# obc-v2_USB-HUB.net
KiCad netlist of a schematic drawn in Altium Designer
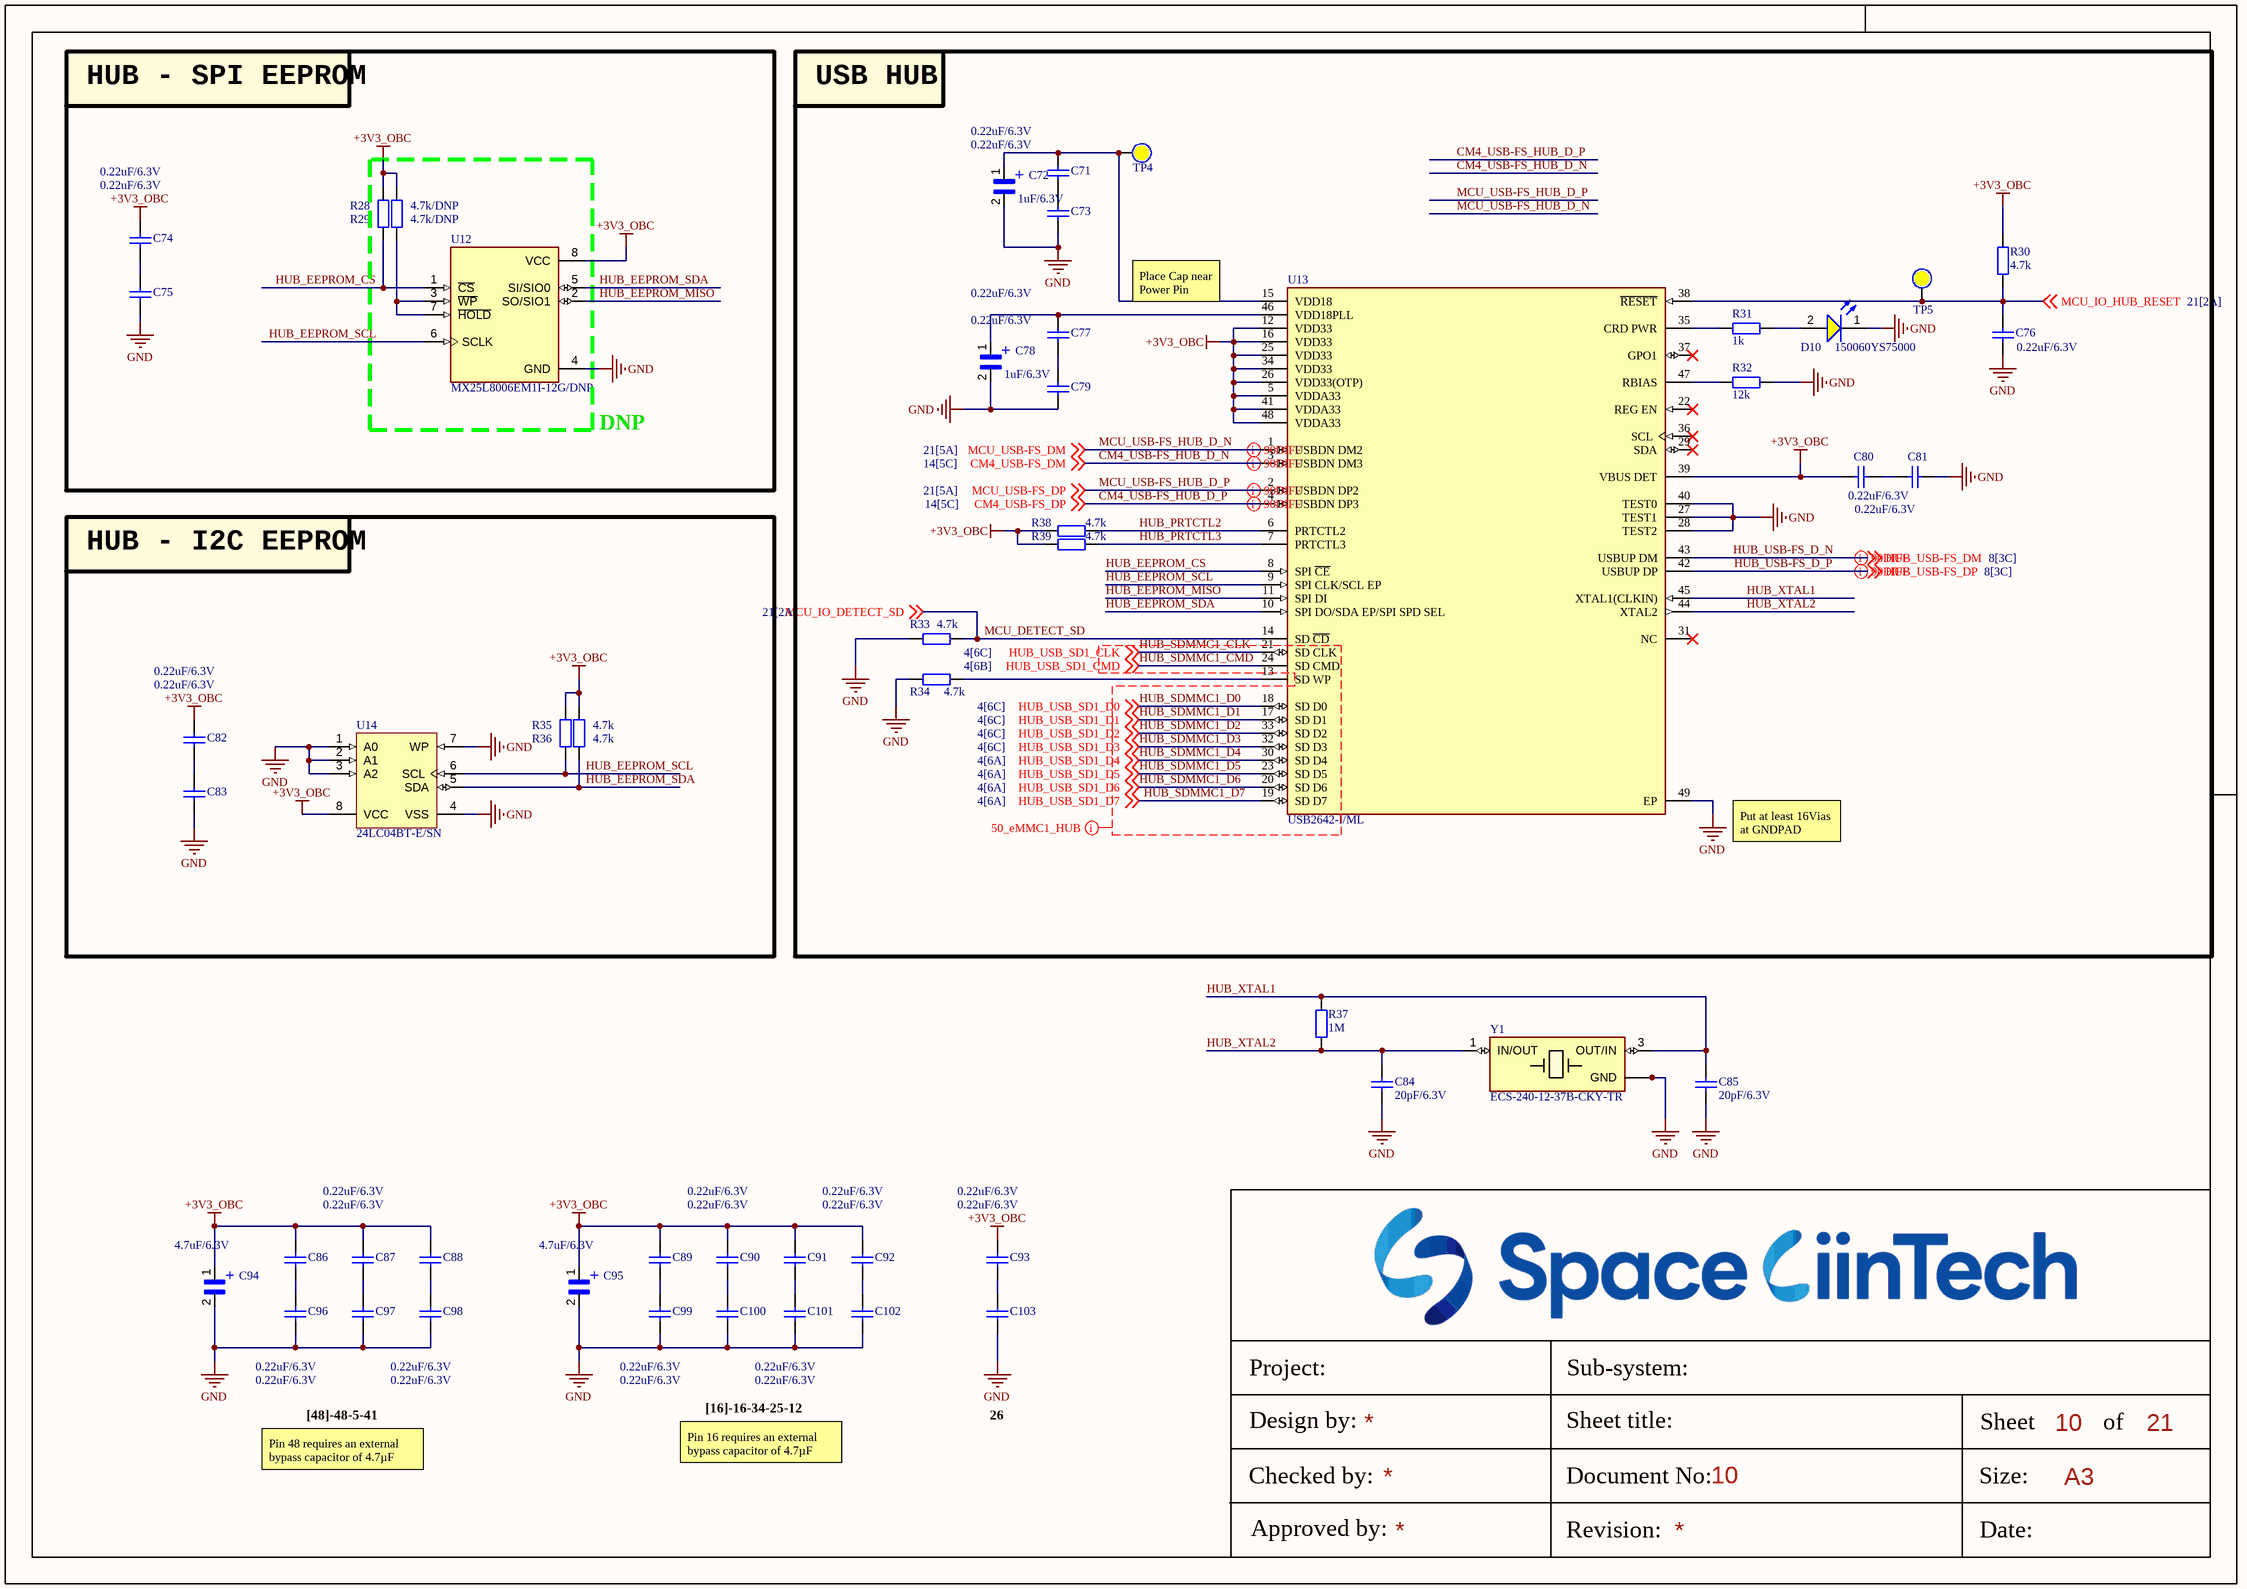
[diagram p0: obc-v2_USB-HUB.SchDoc]

(export (version "E")
  (design (tool "Eeschema 10.0.6"))
  (components
    (comp (ref "C71")
      (value "0.22uF/6.3V")
      (footprint "CAP_C_1005X60")
      (description "CAPC")
      (libsource (lib "Altium_Lib_by_KhueNguyenCreator") (part "Tu 0402 33nF 10V"))
    )
    (comp (ref "C72")
      (value "1uF/6.3V")
      (footprint "CAP_MP_1608X90")
      (description "CAPP")
      (fields (field (name "MP") "TACL335M003RTA"))
      (libsource (lib "TACL335M003RTA") (part "TACL335M003RTA"))
    )
    (comp (ref "C73")
      (value "0.22uF/6.3V")
      (footprint "CAP_C_1005X60")
      (description "CAPC")
      (libsource (lib "Altium_Lib_by_KhueNguyenCreator") (part "Tu 0402 33nF 10V"))
    )
    (comp (ref "C74")
      (value "0.22uF/6.3V")
      (footprint "CAP_C_1005X60")
      (description "CAPC")
      (libsource (lib "Altium_Lib_by_KhueNguyenCreator") (part "Tu 0402 33nF 10V"))
    )
    (comp (ref "C75")
      (value "0.22uF/6.3V")
      (footprint "CAP_C_1005X60")
      (description "CAPC")
      (libsource (lib "Altium_Lib_by_KhueNguyenCreator") (part "Tu 0402 33nF 10V"))
    )
    (comp (ref "C76")
      (value "0.22uF/6.3V")
      (footprint "CAP_C_1005X60")
      (description "CAPC")
      (libsource (lib "Altium_Lib_by_KhueNguyenCreator") (part "Tu 0402 33nF 10V"))
    )
    (comp (ref "C77")
      (value "0.22uF/6.3V")
      (footprint "CAP_C_1005X60")
      (description "CAPC")
      (libsource (lib "Altium_Lib_by_KhueNguyenCreator") (part "Tu 0402 33nF 10V"))
    )
    (comp (ref "C78")
      (value "1uF/6.3V")
      (footprint "CAP_MP_1608X90")
      (description "CAPP")
      (fields (field (name "MP") "TACL335M003RTA"))
      (libsource (lib "TACL335M003RTA") (part "TACL335M003RTA"))
    )
    (comp (ref "C79")
      (value "0.22uF/6.3V")
      (footprint "CAP_C_1005X60")
      (description "CAPC")
      (libsource (lib "Altium_Lib_by_KhueNguyenCreator") (part "Tu 0402 33nF 10V"))
    )
    (comp (ref "C80")
      (value "0.22uF/6.3V")
      (footprint "CAP_C_1005X60")
      (description "CAPC")
      (libsource (lib "Altium_Lib_by_KhueNguyenCreator") (part "Tu 0402 33nF 10V"))
    )
    (comp (ref "C81")
      (value "0.22uF/6.3V")
      (footprint "CAP_C_1005X60")
      (description "CAPC")
      (libsource (lib "Altium_Lib_by_KhueNguyenCreator") (part "Tu 0402 33nF 10V"))
    )
    (comp (ref "C82")
      (value "0.22uF/6.3V")
      (footprint "CAP_C_1005X60")
      (description "CAPC")
      (libsource (lib "Altium_Lib_by_KhueNguyenCreator") (part "Tu 0402 33nF 10V"))
    )
    (comp (ref "C83")
      (value "0.22uF/6.3V")
      (footprint "CAP_C_1005X60")
      (description "CAPC")
      (libsource (lib "Altium_Lib_by_KhueNguyenCreator") (part "Tu 0402 33nF 10V"))
    )
    (comp (ref "C84")
      (value "20pF/6.3V")
      (footprint "CAP_C_1005X60")
      (description "CAPC")
      (libsource (lib "Altium_Lib_by_KhueNguyenCreator") (part "Tu 0402 33nF 10V"))
    )
    (comp (ref "C85")
      (value "20pF/6.3V")
      (footprint "CAP_C_1005X60")
      (description "CAPC")
      (libsource (lib "Altium_Lib_by_KhueNguyenCreator") (part "Tu 0402 33nF 10V"))
    )
    (comp (ref "C86")
      (value "0.22uF/6.3V")
      (footprint "CAP_C_1005X60")
      (description "CAPC")
      (libsource (lib "Altium_Lib_by_KhueNguyenCreator") (part "Tu 0402 33nF 10V"))
    )
    (comp (ref "C87")
      (value "0.22uF/6.3V")
      (footprint "CAP_C_1005X60")
      (description "CAPC")
      (libsource (lib "Altium_Lib_by_KhueNguyenCreator") (part "Tu 0402 33nF 10V"))
    )
    (comp (ref "C88")
      (value "0.22uF/6.3V")
      (footprint "CAP_C_1005X60")
      (description "CAPC")
      (libsource (lib "Altium_Lib_by_KhueNguyenCreator") (part "Tu 0402 33nF 10V"))
    )
    (comp (ref "C89")
      (value "0.22uF/6.3V")
      (footprint "CAP_C_1005X60")
      (description "CAPC")
      (libsource (lib "Altium_Lib_by_KhueNguyenCreator") (part "Tu 0402 33nF 10V"))
    )
    (comp (ref "C90")
      (value "0.22uF/6.3V")
      (footprint "CAP_C_1005X60")
      (description "CAPC")
      (libsource (lib "Altium_Lib_by_KhueNguyenCreator") (part "Tu 0402 33nF 10V"))
    )
    (comp (ref "C91")
      (value "0.22uF/6.3V")
      (footprint "CAP_C_1005X60")
      (description "CAPC")
      (libsource (lib "Altium_Lib_by_KhueNguyenCreator") (part "Tu 0402 33nF 10V"))
    )
    (comp (ref "C92")
      (value "0.22uF/6.3V")
      (footprint "CAP_C_1005X60")
      (description "CAPC")
      (libsource (lib "Altium_Lib_by_KhueNguyenCreator") (part "Tu 0402 33nF 10V"))
    )
    (comp (ref "C93")
      (value "0.22uF/6.3V")
      (footprint "CAP_C_1005X60")
      (description "CAPC")
      (libsource (lib "Altium_Lib_by_KhueNguyenCreator") (part "Tu 0402 33nF 10V"))
    )
    (comp (ref "C94")
      (value "4.7uF/6.3V")
      (footprint "CAP_MP_1608X90")
      (description "CAPP")
      (fields (field (name "MP") "TACL335M003RTA"))
      (libsource (lib "TACL335M003RTA") (part "TACL335M003RTA"))
    )
    (comp (ref "C95")
      (value "4.7uF/6.3V")
      (footprint "CAP_MP_1608X90")
      (description "CAPP")
      (fields (field (name "MP") "TACL335M003RTA"))
      (libsource (lib "TACL335M003RTA") (part "TACL335M003RTA"))
    )
    (comp (ref "C96")
      (value "0.22uF/6.3V")
      (footprint "CAP_C_1005X60")
      (description "CAPC")
      (libsource (lib "Altium_Lib_by_KhueNguyenCreator") (part "Tu 0402 33nF 10V"))
    )
    (comp (ref "C97")
      (value "0.22uF/6.3V")
      (footprint "CAP_C_1005X60")
      (description "CAPC")
      (libsource (lib "Altium_Lib_by_KhueNguyenCreator") (part "Tu 0402 33nF 10V"))
    )
    (comp (ref "C98")
      (value "0.22uF/6.3V")
      (footprint "CAP_C_1005X60")
      (description "CAPC")
      (libsource (lib "Altium_Lib_by_KhueNguyenCreator") (part "Tu 0402 33nF 10V"))
    )
    (comp (ref "C99")
      (value "0.22uF/6.3V")
      (footprint "CAP_C_1005X60")
      (description "CAPC")
      (libsource (lib "Altium_Lib_by_KhueNguyenCreator") (part "Tu 0402 33nF 10V"))
    )
    (comp (ref "C100")
      (value "0.22uF/6.3V")
      (footprint "CAP_C_1005X60")
      (description "CAPC")
      (libsource (lib "Altium_Lib_by_KhueNguyenCreator") (part "Tu 0402 33nF 10V"))
    )
    (comp (ref "C101")
      (value "0.22uF/6.3V")
      (footprint "CAP_C_1005X60")
      (description "CAPC")
      (libsource (lib "Altium_Lib_by_KhueNguyenCreator") (part "Tu 0402 33nF 10V"))
    )
    (comp (ref "C102")
      (value "0.22uF/6.3V")
      (footprint "CAP_C_1005X60")
      (description "CAPC")
      (libsource (lib "Altium_Lib_by_KhueNguyenCreator") (part "Tu 0402 33nF 10V"))
    )
    (comp (ref "C103")
      (value "0.22uF/6.3V")
      (footprint "CAP_C_1005X60")
      (description "CAPC")
      (libsource (lib "Altium_Lib_by_KhueNguyenCreator") (part "Tu 0402 33nF 10V"))
    )
    (comp (ref "D10")
      (value "150060YS75000")
      (footprint "WL-SMCW_0603_150060xx75000")
      (description "LED YELLOW CLEAR 0603 SMD")
      (libsource (lib "Altium Content Vault") (part "LED_Yellow_2A-1K"))
    )
    (comp (ref "R28")
      (value "4.7k/DNP")
      (footprint "RES_C_1608X60")
      (description "RES")
      (libsource (lib "Altium_Lib_by_KhueNguyenCreator") (part "Tro 0603 1% 10k"))
    )
    (comp (ref "R29")
      (value "4.7k/DNP")
      (footprint "RES_C_1608X60")
      (description "RES")
      (libsource (lib "Altium_Lib_by_KhueNguyenCreator") (part "Tro 0603 1% 10k"))
    )
    (comp (ref "R30")
      (value "4.7k")
      (footprint "RES_C_1608X60")
      (description "RES")
      (libsource (lib "Altium_Lib_by_KhueNguyenCreator") (part "Tro 0603 1% 10k"))
    )
    (comp (ref "R31")
      (value "1k")
      (footprint "RES_C_1608X60")
      (description "RES")
      (libsource (lib "Altium_Lib_by_KhueNguyenCreator") (part "Tro 0603 1% 10k"))
    )
    (comp (ref "R32")
      (value "12k")
      (footprint "RES_C_1608X60")
      (description "RES SMD 12K OHM 1% 1/10W 0603, P/N: ERJ-3EKF1202V")
      (libsource (lib "Altium_Lib_by_KhueNguyenCreator") (part "Tro 0603 1% 1k"))
    )
    (comp (ref "R33")
      (value "4.7k")
      (footprint "RES_C_1608X60")
      (description "RES")
      (libsource (lib "Altium_Lib_by_KhueNguyenCreator") (part "Tro 0603 1% 10k"))
    )
    (comp (ref "R34")
      (value "4.7k")
      (footprint "RES_C_1608X60")
      (description "RES")
      (libsource (lib "Altium_Lib_by_KhueNguyenCreator") (part "Tro 0603 1% 10k"))
    )
    (comp (ref "R35")
      (value "4.7k")
      (footprint "RES_C_1608X60")
      (description "RES")
      (libsource (lib "Altium_Lib_by_KhueNguyenCreator") (part "Tro 0603 1% 10k"))
    )
    (comp (ref "R36")
      (value "4.7k")
      (footprint "RES_C_1608X60")
      (description "RES")
      (libsource (lib "Altium_Lib_by_KhueNguyenCreator") (part "Tro 0603 1% 10k"))
    )
    (comp (ref "R37")
      (value "1M")
      (footprint "RES_C_1608X60")
      (description "RES SMD 12K OHM 1% 1/10W 0603, P/N: ERJ-3EKF1202V")
      (libsource (lib "Altium_Lib_by_KhueNguyenCreator") (part "Tro 0603 1% 1k"))
    )
    (comp (ref "R38")
      (value "4.7k")
      (footprint "RES_C_1608X60")
      (description "RES")
      (libsource (lib "Altium_Lib_by_KhueNguyenCreator") (part "Tro 0603 1% 10k"))
    )
    (comp (ref "R39")
      (value "4.7k")
      (footprint "RES_C_1608X60")
      (description "RES")
      (libsource (lib "Altium_Lib_by_KhueNguyenCreator") (part "Tro 0603 1% 10k"))
    )
    (comp (ref "TP4")
      (value "~")
      (footprint "Test Point 1 Side")
      (description "Test Point")
      (libsource (lib "BYTECH_HW_LIB_2019 (1)") (part "Test Point"))
    )
    (comp (ref "TP5")
      (value "~")
      (footprint "Test Point 1 Side")
      (description "Test Point")
      (libsource (lib "") (part "Test Point_1"))
    )
    (comp (ref "U12")
      (value "MX25L8006EM1I-12G/DNP")
      (footprint "SOIC127P602X173-8N")
      (description "FLASH - NOR Memory IC 8Mb (1M x 8) SPI 86 MHz 8-SOP")
      (fields (field (name "MF") "Macronix") (field (name "MP") "MX25L8006EM1I-12G"))
      (libsource (lib "MX25L8006EM1I-12G") (part "MX25L8006EM1I-12G"))
    )
    (comp (ref "U13")
      (value "USB2642-I/ML")
      (footprint "FP-48QFN-5304-7x7B-IPC_A")
      (description "IC INTERFACE SPECIALIZED 48QFN")
      (libsource (lib "Altium Content Vault") (part "374cda126ac25a5c5b8599f60553335"))
    )
    (comp (ref "U14")
      (value "24LC04BT-E/SN")
      (footprint "SOIC-SN8_L")
      (description "4Kbit, 400kHz, 2.5V, I2C Serial EEPROM, 8-Pin SOIC 150mil, Extended Temperature, Tape and Reel")
      (libsource (lib "Altium Content Vault") (part "MEM-SEEPROM-34AA02-IL8"))
    )
    (comp (ref "Y1")
      (value "ECS-240-12-37B-CKY-TR")
      (footprint "XTAL_ECS-240-12-37B-CKY-TR")
      (libsource (lib "ECS-240-12-37B-CKY-TR") (part "ECS-240-12-37B-CKY-TR"))
    )
  )
  (nets
    (net (code "1") (name "+3V3_OBC") (class "Default")
      (node (ref "C74") (pin "1") (pinfunction "1_1") (pintype "passive"))
      (node (ref "C80") (pin "1") (pinfunction "1_1") (pintype "passive"))
      (node (ref "C82") (pin "1") (pinfunction "1_1") (pintype "passive"))
      (node (ref "C86") (pin "1") (pinfunction "1_1") (pintype "passive"))
      (node (ref "C87") (pin "1") (pinfunction "1_1") (pintype "passive"))
      (node (ref "C88") (pin "1") (pinfunction "1_1") (pintype "passive"))
      (node (ref "C89") (pin "1") (pinfunction "1_1") (pintype "passive"))
      (node (ref "C90") (pin "1") (pinfunction "1_1") (pintype "passive"))
      (node (ref "C91") (pin "1") (pinfunction "1_1") (pintype "passive"))
      (node (ref "C92") (pin "1") (pinfunction "1_1") (pintype "passive"))
      (node (ref "C93") (pin "1") (pinfunction "1_1") (pintype "passive"))
      (node (ref "C94") (pin "1") (pinfunction "1_1") (pintype "passive"))
      (node (ref "C95") (pin "1") (pinfunction "1_1") (pintype "passive"))
      (node (ref "R28") (pin "2") (pinfunction "2_2") (pintype "passive"))
      (node (ref "R29") (pin "2") (pinfunction "2_2") (pintype "passive"))
      (node (ref "R30") (pin "1") (pinfunction "1_1") (pintype "passive"))
      (node (ref "R35") (pin "2") (pinfunction "2_2") (pintype "passive"))
      (node (ref "R36") (pin "2") (pinfunction "2_2") (pintype "passive"))
      (node (ref "R38") (pin "1") (pinfunction "1_1") (pintype "passive"))
      (node (ref "R39") (pin "1") (pinfunction "1_1") (pintype "passive"))
      (node (ref "U12") (pin "8") (pinfunction "VCC_8") (pintype "power_in"))
      (node (ref "U13") (pin "12") (pinfunction "VDD33_12") (pintype "power_in"))
      (node (ref "U13") (pin "16") (pinfunction "VDD33_16") (pintype "power_in"))
      (node (ref "U13") (pin "25") (pinfunction "VDD33_25") (pintype "power_in"))
      (node (ref "U13") (pin "26") (pinfunction "VDD33(OTP)_26") (pintype "power_in"))
      (node (ref "U13") (pin "34") (pinfunction "VDD33_34") (pintype "power_in"))
      (node (ref "U13") (pin "39") (pinfunction "VBUS_DET_39") (pintype "power_in"))
      (node (ref "U13") (pin "41") (pinfunction "VDDA33_41") (pintype "power_in"))
      (node (ref "U13") (pin "48") (pinfunction "VDDA33_48") (pintype "power_in"))
      (node (ref "U13") (pin "5") (pinfunction "VDDA33_5") (pintype "power_in"))
      (node (ref "U14") (pin "8") (pinfunction "VCC_8") (pintype "power_in"))
    )
    (net (code "2") (name "/HUB_EEPROM_CS") (class "Default")
      (node (ref "R29") (pin "1") (pinfunction "1_1") (pintype "passive"))
      (node (ref "U12") (pin "1") (pinfunction "~{CS}_1") (pintype "input"))
      (node (ref "U13") (pin "8") (pinfunction "SPI_~{CE}_8") (pintype "input"))
    )
    (net (code "3") (name "/HUB_EEPROM_MISO") (class "Default")
      (node (ref "U12") (pin "2") (pinfunction "SO/SIO1_2") (pintype "bidirectional"))
      (node (ref "U13") (pin "11") (pinfunction "SPI_DI_11") (pintype "input"))
    )
    (net (code "4") (name "/HUB_EEPROM_SCL") (class "Default")
      (node (ref "R36") (pin "1") (pinfunction "1_1") (pintype "passive"))
      (node (ref "U12") (pin "6") (pinfunction "SCLK_6") (pintype "input"))
      (node (ref "U13") (pin "9") (pinfunction "SPI_CLK/SCL_EP_9") (pintype "input"))
      (node (ref "U14") (pin "6") (pinfunction "SCL_6") (pintype "input"))
    )
    (net (code "5") (name "/HUB_EEPROM_SDA") (class "Default")
      (node (ref "R35") (pin "1") (pinfunction "1_1") (pintype "passive"))
      (node (ref "U12") (pin "5") (pinfunction "SI/SIO0_5") (pintype "bidirectional"))
      (node (ref "U13") (pin "10") (pinfunction "SPI_DO/SDA_EP/SPI_SPD_SEL_10") (pintype "input"))
      (node (ref "U14") (pin "5") (pinfunction "SDA_5") (pintype "bidirectional"))
    )
    (net (code "6") (name "/HUB_PRTCTL2") (class "Default")
      (node (ref "R38") (pin "2") (pinfunction "2_2") (pintype "passive"))
      (node (ref "U13") (pin "6") (pinfunction "PRTCTL2_6") (pintype "passive"))
    )
    (net (code "7") (name "/HUB_PRTCTL3") (class "Default")
      (node (ref "R39") (pin "2") (pinfunction "2_2") (pintype "passive"))
      (node (ref "U13") (pin "7") (pinfunction "PRTCTL3_7") (pintype "passive"))
    )
    (net (code "8") (name "/HUB_XTAL1") (class "Default")
      (node (ref "C85") (pin "2") (pinfunction "2_2") (pintype "passive"))
      (node (ref "R37") (pin "2") (pinfunction "2_2") (pintype "passive"))
      (node (ref "U13") (pin "45") (pinfunction "XTAL1(CLKIN)_45") (pintype "input"))
      (node (ref "Y1") (pin "3") (pinfunction "OUT/IN_3") (pintype "bidirectional"))
    )
    (net (code "9") (name "/HUB_XTAL2") (class "Default")
      (node (ref "C84") (pin "2") (pinfunction "2_2") (pintype "passive"))
      (node (ref "R37") (pin "1") (pinfunction "1_1") (pintype "passive"))
      (node (ref "U13") (pin "44") (pinfunction "XTAL2_44") (pintype "output"))
      (node (ref "Y1") (pin "1") (pinfunction "IN/OUT_1") (pintype "bidirectional"))
    )
    (net (code "10") (name "CM4_USB-FS_DM") (class "Default")
      (node (ref "U13") (pin "3") (pinfunction "USBDN_DM3_3") (pintype "bidirectional"))
    )
    (net (code "11") (name "CM4_USB-FS_DP") (class "Default")
      (node (ref "U13") (pin "4") (pinfunction "USBDN_DP3_4") (pintype "bidirectional"))
    )
    (net (code "12") (name "GND") (class "Default")
      (node (ref "C100") (pin "2") (pinfunction "2_2") (pintype "passive"))
      (node (ref "C101") (pin "2") (pinfunction "2_2") (pintype "passive"))
      (node (ref "C102") (pin "2") (pinfunction "2_2") (pintype "passive"))
      (node (ref "C103") (pin "2") (pinfunction "2_2") (pintype "passive"))
      (node (ref "C72") (pin "2") (pinfunction "2_2") (pintype "passive"))
      (node (ref "C73") (pin "1") (pinfunction "1_1") (pintype "passive"))
      (node (ref "C75") (pin "2") (pinfunction "2_2") (pintype "passive"))
      (node (ref "C76") (pin "2") (pinfunction "2_2") (pintype "passive"))
      (node (ref "C78") (pin "2") (pinfunction "2_2") (pintype "passive"))
      (node (ref "C79") (pin "1") (pinfunction "1_1") (pintype "passive"))
      (node (ref "C81") (pin "2") (pinfunction "2_2") (pintype "passive"))
      (node (ref "C83") (pin "2") (pinfunction "2_2") (pintype "passive"))
      (node (ref "C84") (pin "1") (pinfunction "1_1") (pintype "passive"))
      (node (ref "C85") (pin "1") (pinfunction "1_1") (pintype "passive"))
      (node (ref "C94") (pin "2") (pinfunction "2_2") (pintype "passive"))
      (node (ref "C95") (pin "2") (pinfunction "2_2") (pintype "passive"))
      (node (ref "C96") (pin "2") (pinfunction "2_2") (pintype "passive"))
      (node (ref "C97") (pin "2") (pinfunction "2_2") (pintype "passive"))
      (node (ref "C98") (pin "2") (pinfunction "2_2") (pintype "passive"))
      (node (ref "C99") (pin "2") (pinfunction "2_2") (pintype "passive"))
      (node (ref "D10") (pin "1") (pinfunction "K_1") (pintype "passive"))
      (node (ref "R32") (pin "2") (pinfunction "2_2") (pintype "passive"))
      (node (ref "R33") (pin "1") (pinfunction "1_1") (pintype "passive"))
      (node (ref "R34") (pin "1") (pinfunction "1_1") (pintype "passive"))
      (node (ref "U12") (pin "4") (pinfunction "GND_4") (pintype "power_in"))
      (node (ref "U13") (pin "27") (pinfunction "TEST1_27") (pintype "passive"))
      (node (ref "U13") (pin "28") (pinfunction "TEST2_28") (pintype "passive"))
      (node (ref "U13") (pin "40") (pinfunction "TEST0_40") (pintype "passive"))
      (node (ref "U13") (pin "49") (pinfunction "EP_49") (pintype "power_in"))
      (node (ref "U14") (pin "1") (pinfunction "A0_1") (pintype "input"))
      (node (ref "U14") (pin "2") (pinfunction "A1_2") (pintype "input"))
      (node (ref "U14") (pin "3") (pinfunction "A2_3") (pintype "input"))
      (node (ref "U14") (pin "4") (pinfunction "VSS_4") (pintype "power_in"))
      (node (ref "U14") (pin "7") (pinfunction "WP_7") (pintype "input"))
      (node (ref "Y1") (pin "2") (pinfunction "GND_2") (pintype "power_in"))
      (node (ref "Y1") (pin "4") (pinfunction "GND_4") (pintype "power_in"))
    )
    (net (code "13") (name "HUB_USB-FS_DM") (class "Default")
      (node (ref "U13") (pin "43") (pinfunction "USBUP_DM_43") (pintype "passive"))
    )
    (net (code "14") (name "HUB_USB-FS_DP") (class "Default")
      (node (ref "U13") (pin "42") (pinfunction "USBUP_DP_42") (pintype "passive"))
    )
    (net (code "15") (name "HUB_USB_SD1_CLK") (class "Default")
      (node (ref "U13") (pin "21") (pinfunction "SD_CLK_21") (pintype "bidirectional"))
    )
    (net (code "16") (name "HUB_USB_SD1_CMD") (class "Default")
      (node (ref "U13") (pin "24") (pinfunction "SD_CMD_24") (pintype "passive"))
    )
    (net (code "17") (name "HUB_USB_SD1_D0") (class "Default")
      (node (ref "U13") (pin "18") (pinfunction "SD_D0_18") (pintype "bidirectional"))
    )
    (net (code "18") (name "HUB_USB_SD1_D1") (class "Default")
      (node (ref "U13") (pin "17") (pinfunction "SD_D1_17") (pintype "bidirectional"))
    )
    (net (code "19") (name "HUB_USB_SD1_D2") (class "Default")
      (node (ref "U13") (pin "33") (pinfunction "SD_D2_33") (pintype "bidirectional"))
    )
    (net (code "20") (name "HUB_USB_SD1_D3") (class "Default")
      (node (ref "U13") (pin "32") (pinfunction "SD_D3_32") (pintype "bidirectional"))
    )
    (net (code "21") (name "HUB_USB_SD1_D4") (class "Default")
      (node (ref "U13") (pin "30") (pinfunction "SD_D4_30") (pintype "bidirectional"))
    )
    (net (code "22") (name "HUB_USB_SD1_D5") (class "Default")
      (node (ref "U13") (pin "23") (pinfunction "SD_D5_23") (pintype "bidirectional"))
    )
    (net (code "23") (name "HUB_USB_SD1_D6") (class "Default")
      (node (ref "U13") (pin "20") (pinfunction "SD_D6_20") (pintype "bidirectional"))
    )
    (net (code "24") (name "HUB_USB_SD1_D7") (class "Default")
      (node (ref "U13") (pin "19") (pinfunction "SD_D7_19") (pintype "bidirectional"))
    )
    (net (code "25") (name "MCU_IO_DETECT_SD") (class "Default")
      (node (ref "R33") (pin "2") (pinfunction "2_2") (pintype "passive"))
      (node (ref "U13") (pin "14") (pinfunction "SD_~{CD}_14") (pintype "passive"))
    )
    (net (code "26") (name "MCU_IO_HUB_RESET") (class "Default")
      (node (ref "C76") (pin "1") (pinfunction "1_1") (pintype "passive"))
      (node (ref "R30") (pin "2") (pinfunction "2_2") (pintype "passive"))
      (node (ref "TP5") (pin "0") (pinfunction "0_0") (pintype "passive"))
      (node (ref "U13") (pin "38") (pinfunction "~{RESET}_38") (pintype "input"))
    )
    (net (code "27") (name "MCU_USB-FS_DM") (class "Default")
      (node (ref "U13") (pin "1") (pinfunction "USBDN_DM2_1") (pintype "bidirectional"))
    )
    (net (code "28") (name "MCU_USB-FS_DP") (class "Default")
      (node (ref "U13") (pin "2") (pinfunction "USBDN_DP2_2") (pintype "bidirectional"))
    )
    (net (code "29") (name "Net-(C71-Pad1)") (class "Default")
      (node (ref "C71") (pin "1") (pinfunction "1_1") (pintype "passive"))
      (node (ref "C73") (pin "2") (pinfunction "2_2") (pintype "passive"))
    )
    (net (code "30") (name "Net-(C74-Pad2)") (class "Default")
      (node (ref "C74") (pin "2") (pinfunction "2_2") (pintype "passive"))
      (node (ref "C75") (pin "1") (pinfunction "1_1") (pintype "passive"))
    )
    (net (code "31") (name "Net-(C77-Pad1)") (class "Default")
      (node (ref "C77") (pin "1") (pinfunction "1_1") (pintype "passive"))
      (node (ref "C79") (pin "2") (pinfunction "2_2") (pintype "passive"))
    )
    (net (code "32") (name "Net-(C80-Pad2)") (class "Default")
      (node (ref "C80") (pin "2") (pinfunction "2_2") (pintype "passive"))
      (node (ref "C81") (pin "1") (pinfunction "1_1") (pintype "passive"))
    )
    (net (code "33") (name "Net-(C82-Pad2)") (class "Default")
      (node (ref "C82") (pin "2") (pinfunction "2_2") (pintype "passive"))
      (node (ref "C83") (pin "1") (pinfunction "1_1") (pintype "passive"))
    )
    (net (code "34") (name "Net-(C86-Pad2)") (class "Default")
      (node (ref "C86") (pin "2") (pinfunction "2_2") (pintype "passive"))
      (node (ref "C96") (pin "1") (pinfunction "1_1") (pintype "passive"))
    )
    (net (code "35") (name "Net-(C87-Pad2)") (class "Default")
      (node (ref "C87") (pin "2") (pinfunction "2_2") (pintype "passive"))
      (node (ref "C97") (pin "1") (pinfunction "1_1") (pintype "passive"))
    )
    (net (code "36") (name "Net-(C88-Pad2)") (class "Default")
      (node (ref "C88") (pin "2") (pinfunction "2_2") (pintype "passive"))
      (node (ref "C98") (pin "1") (pinfunction "1_1") (pintype "passive"))
    )
    (net (code "37") (name "Net-(C89-Pad2)") (class "Default")
      (node (ref "C89") (pin "2") (pinfunction "2_2") (pintype "passive"))
      (node (ref "C99") (pin "1") (pinfunction "1_1") (pintype "passive"))
    )
    (net (code "38") (name "Net-(C100-Pad1)") (class "Default")
      (node (ref "C100") (pin "1") (pinfunction "1_1") (pintype "passive"))
      (node (ref "C90") (pin "2") (pinfunction "2_2") (pintype "passive"))
    )
    (net (code "39") (name "Net-(C101-Pad1)") (class "Default")
      (node (ref "C101") (pin "1") (pinfunction "1_1") (pintype "passive"))
      (node (ref "C91") (pin "2") (pinfunction "2_2") (pintype "passive"))
    )
    (net (code "40") (name "Net-(C102-Pad1)") (class "Default")
      (node (ref "C102") (pin "1") (pinfunction "1_1") (pintype "passive"))
      (node (ref "C92") (pin "2") (pinfunction "2_2") (pintype "passive"))
    )
    (net (code "41") (name "Net-(C103-Pad1)") (class "Default")
      (node (ref "C103") (pin "1") (pinfunction "1_1") (pintype "passive"))
      (node (ref "C93") (pin "2") (pinfunction "2_2") (pintype "passive"))
    )
    (net (code "42") (name "Net-(D10-A)") (class "Default")
      (node (ref "D10") (pin "2") (pinfunction "A_2") (pintype "passive"))
      (node (ref "R31") (pin "1") (pinfunction "1_1") (pintype "passive"))
    )
    (net (code "43") (name "Net-(U12-~{HOLD})") (class "Default")
      (node (ref "R28") (pin "1") (pinfunction "1_1") (pintype "passive"))
      (node (ref "U12") (pin "3") (pinfunction "~{WP}_3") (pintype "input"))
      (node (ref "U12") (pin "7") (pinfunction "~{HOLD}_7") (pintype "input"))
    )
    (net (code "44") (name "Net-(U13-CRD_PWR)") (class "Default")
      (node (ref "R31") (pin "2") (pinfunction "2_2") (pintype "passive"))
      (node (ref "U13") (pin "35") (pinfunction "CRD_PWR_35") (pintype "passive"))
    )
    (net (code "45") (name "Net-(U13-RBIAS)") (class "Default")
      (node (ref "R32") (pin "1") (pinfunction "1_1") (pintype "passive"))
      (node (ref "U13") (pin "47") (pinfunction "RBIAS_47") (pintype "passive"))
    )
    (net (code "46") (name "Net-(U13-SD_WP)") (class "Default")
      (node (ref "R34") (pin "2") (pinfunction "2_2") (pintype "passive"))
      (node (ref "U13") (pin "13") (pinfunction "SD_WP_13") (pintype "passive"))
    )
    (net (code "47") (name "Net-(U13-VDD18)") (class "Default")
      (node (ref "C71") (pin "2") (pinfunction "2_2") (pintype "passive"))
      (node (ref "C72") (pin "1") (pinfunction "1_1") (pintype "passive"))
      (node (ref "TP4") (pin "0") (pinfunction "0_0") (pintype "passive"))
      (node (ref "U13") (pin "15") (pinfunction "VDD18_15") (pintype "power_in"))
    )
    (net (code "48") (name "Net-(U13-VDD18PLL)") (class "Default")
      (node (ref "C77") (pin "2") (pinfunction "2_2") (pintype "passive"))
      (node (ref "C78") (pin "1") (pinfunction "1_1") (pintype "passive"))
      (node (ref "U13") (pin "46") (pinfunction "VDD18PLL_46") (pintype "power_in"))
    )
    (net (code "49") (name "unconnected-(U13-GPO1-Pad37)") (class "Default")
      (node (ref "U13") (pin "37") (pinfunction "GPO1_37") (pintype "bidirectional+no_connect"))
    )
    (net (code "50") (name "unconnected-(U13-NC-Pad31)") (class "Default")
      (node (ref "U13") (pin "31") (pinfunction "NC_31") (pintype "passive+no_connect"))
    )
    (net (code "51") (name "unconnected-(U13-REG_EN-Pad22)") (class "Default")
      (node (ref "U13") (pin "22") (pinfunction "REG_EN_22") (pintype "input+no_connect"))
    )
    (net (code "52") (name "unconnected-(U13-SCL-Pad36)") (class "Default")
      (node (ref "U13") (pin "36") (pinfunction "SCL_36") (pintype "input+no_connect"))
    )
    (net (code "53") (name "unconnected-(U13-SDA-Pad29)") (class "Default")
      (node (ref "U13") (pin "29") (pinfunction "SDA_29") (pintype "bidirectional+no_connect"))
    )
  )
)
